# EV75E52A_R3_3-Power.net
KiCad netlist of a schematic drawn in Altium Designer
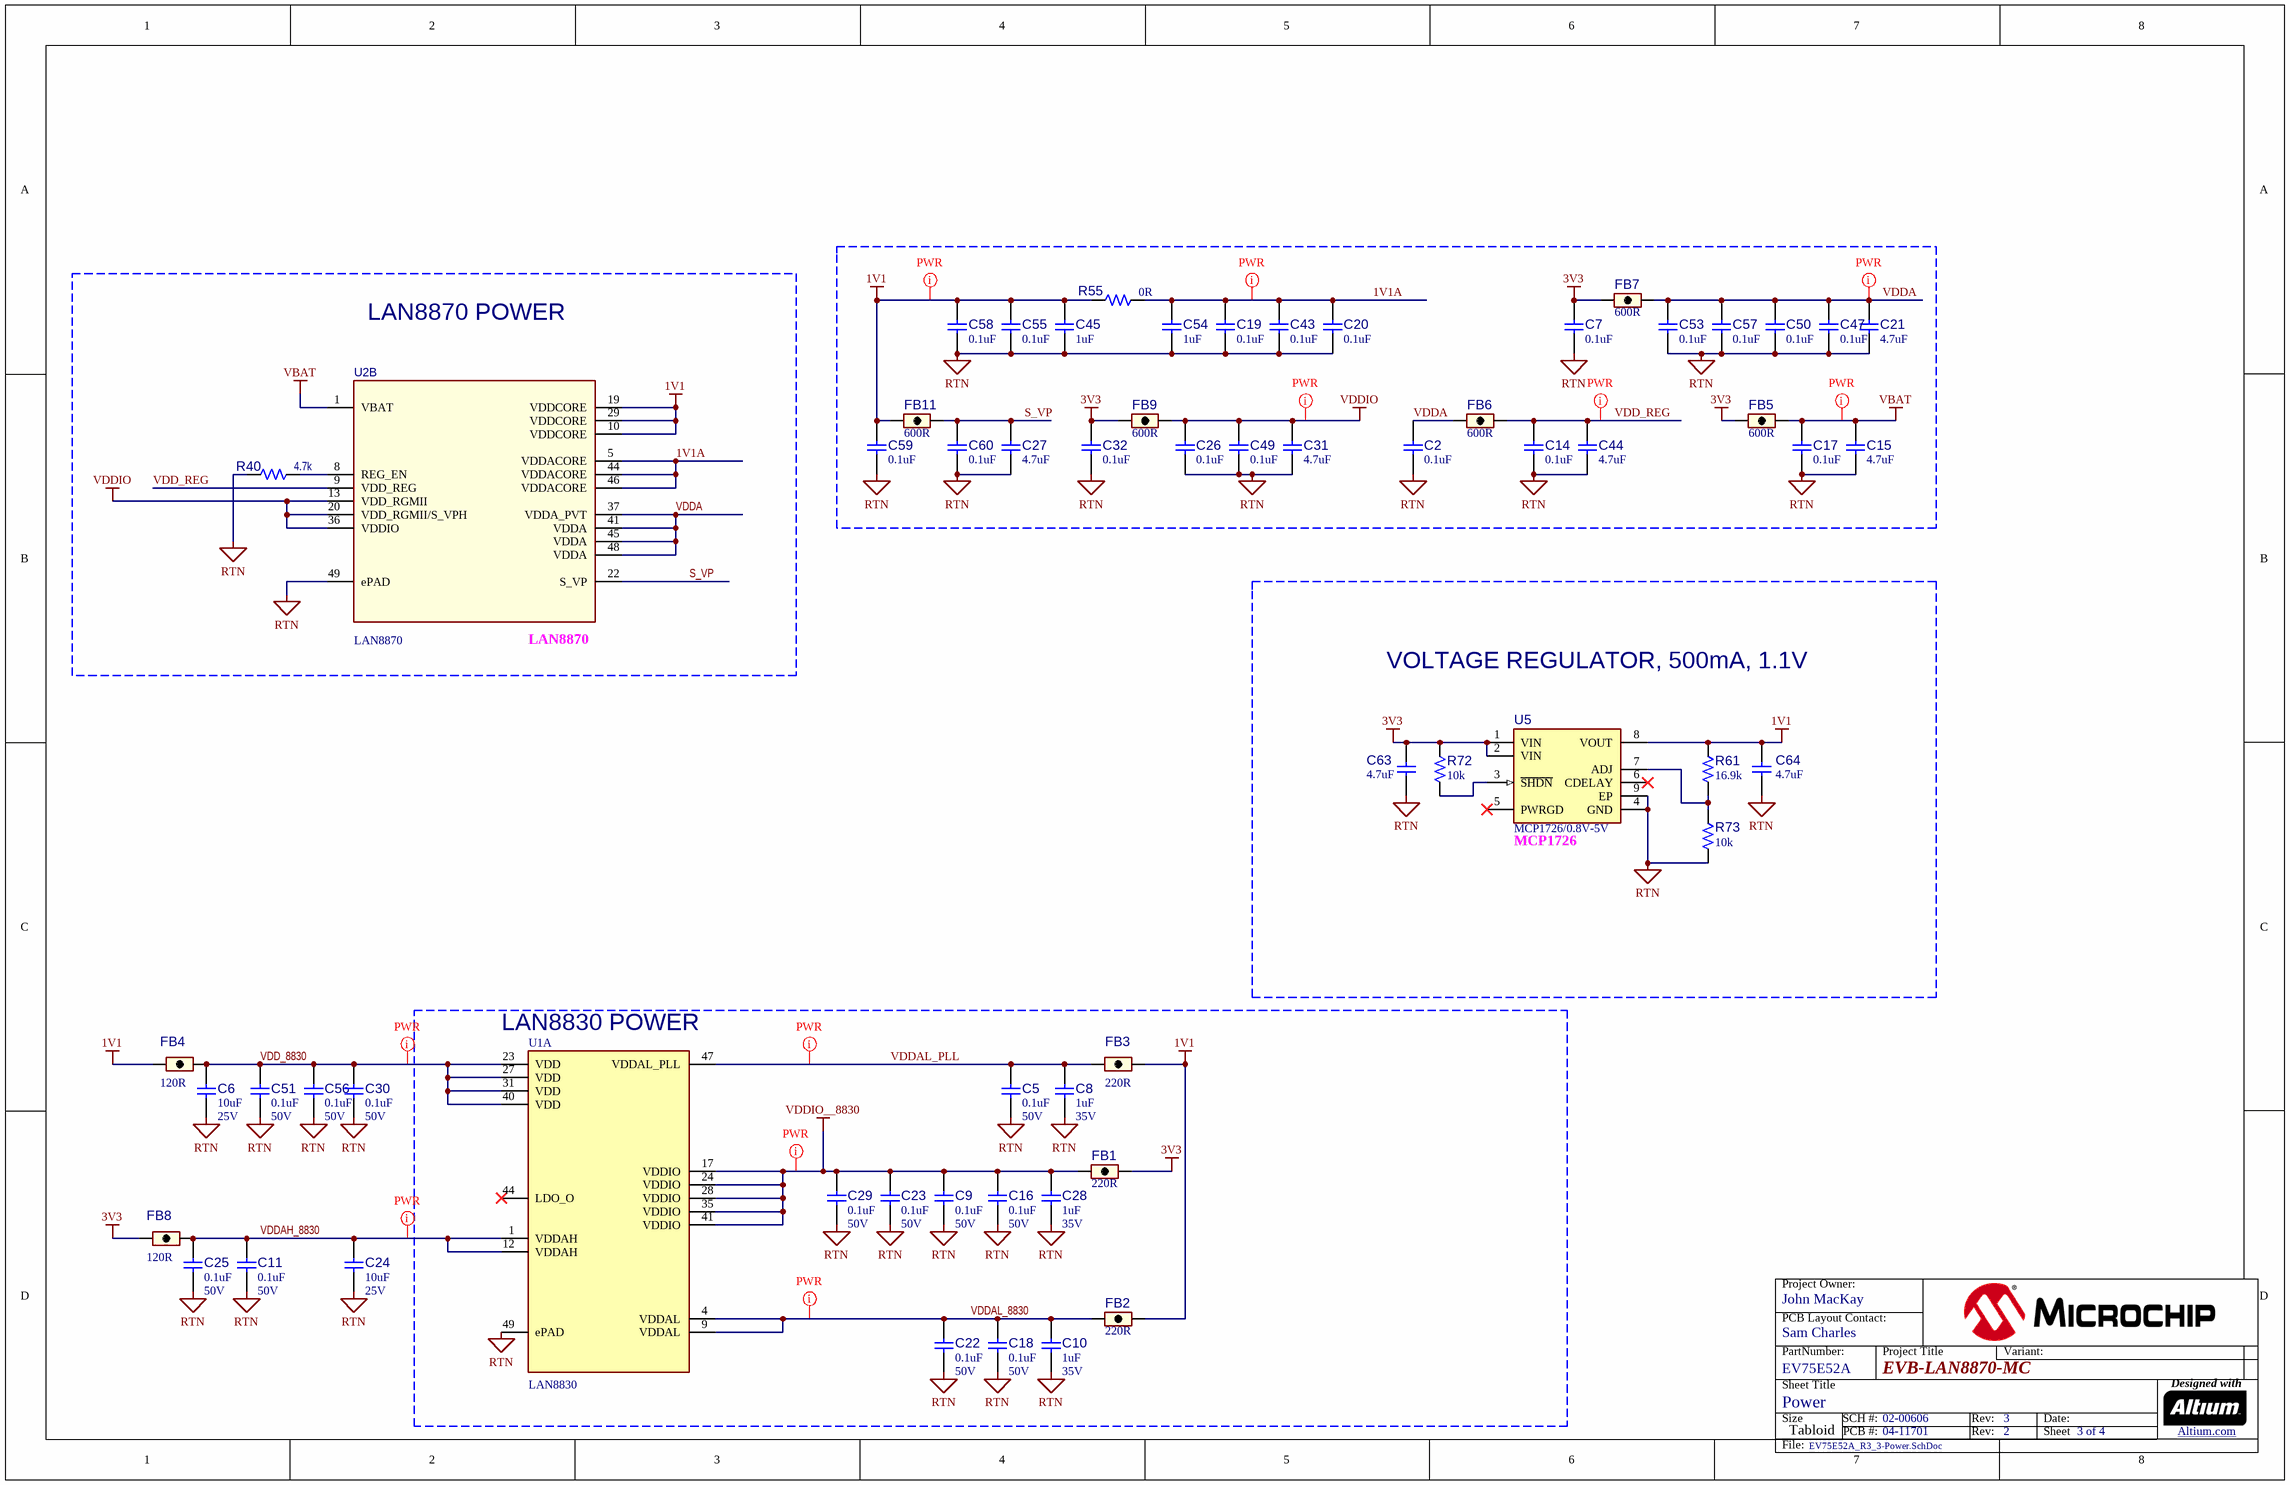
[diagram p0: EV75E52A_R3_3-Power.SchDoc]

(export (version "E")
  (design (tool "Eeschema 10.0.6"))
  (components
    (comp (ref "C2")
      (value "0.1uF")
      (footprint "CAP_C_0402")
      (fields
        (field (name "VOLTAGE") "35V")
        (field (name "TOLERANCE") "10%")
        (field (name "Comment") "Capacitor NP")
        (field (name "OWNER") "Sam Charles")
      )
      (libsource (lib "") (part "Capacitor NP_1"))
    )
    (comp (ref "C5")
      (value "0.1uF")
      (footprint "CAP_C_0402")
      (description "Capacitor")
      (fields
        (field (name "VOLTAGE") "50V")
        (field (name "TOLERANCE") "10%")
        (field (name "Comment") "Capacitor NP")
        (field (name "OWNER") "Jamus Griego")
      )
      (libsource (lib "MCHP-CDB") (part "Capacitor NP"))
    )
    (comp (ref "C6")
      (value "10uF")
      (footprint "CAP_C_0603")
      (description "Capacitor")
      (fields
        (field (name "VOLTAGE") "25V")
        (field (name "TOLERANCE") "±20%")
        (field (name "Comment") "Capacitor NP")
        (field (name "OWNER") "Tim Moffat")
      )
      (libsource (lib "MCHP-CDB") (part "Capacitor NP"))
    )
    (comp (ref "C7")
      (value "0.1uF")
      (footprint "CAP_C_0402")
      (fields
        (field (name "VOLTAGE") "35V")
        (field (name "TOLERANCE") "10%")
        (field (name "Comment") "Capacitor NP")
        (field (name "OWNER") "Sam Charles")
      )
      (libsource (lib "") (part "Capacitor NP_1"))
    )
    (comp (ref "C8")
      (value "1uF")
      (footprint "CAP_C_0402")
      (description "Capacitor")
      (fields
        (field (name "VOLTAGE") "35V")
        (field (name "TOLERANCE") "10%")
        (field (name "Comment") "Capacitor NP")
        (field (name "OWNER") "Sam Charles")
      )
      (libsource (lib "MCHP-CDB") (part "Capacitor NP"))
    )
    (comp (ref "C9")
      (value "0.1uF")
      (footprint "CAP_C_0402")
      (description "Capacitor")
      (fields
        (field (name "VOLTAGE") "50V")
        (field (name "TOLERANCE") "10%")
        (field (name "Comment") "Capacitor NP")
        (field (name "OWNER") "Jamus Griego")
      )
      (libsource (lib "MCHP-CDB") (part "Capacitor NP"))
    )
    (comp (ref "C10")
      (value "1uF")
      (footprint "CAP_C_0402")
      (description "Capacitor")
      (fields
        (field (name "VOLTAGE") "35V")
        (field (name "TOLERANCE") "10%")
        (field (name "Comment") "Capacitor NP")
        (field (name "OWNER") "Sam Charles")
      )
      (libsource (lib "MCHP-CDB") (part "Capacitor NP"))
    )
    (comp (ref "C11")
      (value "0.1uF")
      (footprint "CAP_C_0402")
      (description "Capacitor")
      (fields
        (field (name "VOLTAGE") "50V")
        (field (name "TOLERANCE") "10%")
        (field (name "Comment") "Capacitor NP")
        (field (name "OWNER") "Jamus Griego")
      )
      (libsource (lib "MCHP-CDB") (part "Capacitor NP"))
    )
    (comp (ref "C14")
      (value "0.1uF")
      (footprint "CAP_C_0402")
      (fields
        (field (name "VOLTAGE") "35V")
        (field (name "TOLERANCE") "10%")
        (field (name "Comment") "Capacitor NP")
        (field (name "OWNER") "Sam Charles")
      )
      (libsource (lib "") (part "Capacitor NP_1"))
    )
    (comp (ref "C15")
      (value "4.7uF")
      (footprint "CAP_C_0402")
      (fields
        (field (name "VOLTAGE") "6.3V")
        (field (name "TOLERANCE") "20%")
        (field (name "Comment") "Capacitor NP")
        (field (name "OWNER") "Tad Ahlvers")
      )
      (libsource (lib "") (part "Capacitor NP_1"))
    )
    (comp (ref "C16")
      (value "0.1uF")
      (footprint "CAP_C_0402")
      (description "Capacitor")
      (fields
        (field (name "VOLTAGE") "50V")
        (field (name "TOLERANCE") "10%")
        (field (name "Comment") "Capacitor NP")
        (field (name "OWNER") "Jamus Griego")
      )
      (libsource (lib "MCHP-CDB") (part "Capacitor NP"))
    )
    (comp (ref "C17")
      (value "0.1uF")
      (footprint "CAP_C_0402")
      (fields
        (field (name "VOLTAGE") "35V")
        (field (name "TOLERANCE") "10%")
        (field (name "Comment") "Capacitor NP")
        (field (name "OWNER") "Sam Charles")
      )
      (libsource (lib "") (part "Capacitor NP_1"))
    )
    (comp (ref "C18")
      (value "0.1uF")
      (footprint "CAP_C_0402")
      (description "Capacitor")
      (fields
        (field (name "VOLTAGE") "50V")
        (field (name "TOLERANCE") "10%")
        (field (name "Comment") "Capacitor NP")
        (field (name "OWNER") "Jamus Griego")
      )
      (libsource (lib "MCHP-CDB") (part "Capacitor NP"))
    )
    (comp (ref "C19")
      (value "0.1uF")
      (footprint "CAP_C_0402")
      (fields
        (field (name "VOLTAGE") "35V")
        (field (name "TOLERANCE") "10%")
        (field (name "Comment") "Capacitor NP")
        (field (name "OWNER") "Sam Charles")
      )
      (libsource (lib "") (part "Capacitor NP_1"))
    )
    (comp (ref "C20")
      (value "0.1uF")
      (footprint "CAP_C_0402")
      (fields
        (field (name "VOLTAGE") "35V")
        (field (name "TOLERANCE") "10%")
        (field (name "Comment") "Capacitor NP")
        (field (name "OWNER") "Sam Charles")
      )
      (libsource (lib "") (part "Capacitor NP_1"))
    )
    (comp (ref "C21")
      (value "4.7uF")
      (footprint "CAP_C_0402")
      (fields
        (field (name "VOLTAGE") "6.3V")
        (field (name "TOLERANCE") "20%")
        (field (name "Comment") "Capacitor NP")
        (field (name "OWNER") "Tad Ahlvers")
      )
      (libsource (lib "") (part "Capacitor NP_1"))
    )
    (comp (ref "C22")
      (value "0.1uF")
      (footprint "CAP_C_0402")
      (description "Capacitor")
      (fields
        (field (name "VOLTAGE") "50V")
        (field (name "TOLERANCE") "10%")
        (field (name "Comment") "Capacitor NP")
        (field (name "OWNER") "Jamus Griego")
      )
      (libsource (lib "MCHP-CDB") (part "Capacitor NP"))
    )
    (comp (ref "C23")
      (value "0.1uF")
      (footprint "CAP_C_0402")
      (description "Capacitor")
      (fields
        (field (name "VOLTAGE") "50V")
        (field (name "TOLERANCE") "10%")
        (field (name "Comment") "Capacitor NP")
        (field (name "OWNER") "Jamus Griego")
      )
      (libsource (lib "MCHP-CDB") (part "Capacitor NP"))
    )
    (comp (ref "C24")
      (value "10uF")
      (footprint "CAP_C_0603")
      (description "Capacitor")
      (fields
        (field (name "VOLTAGE") "25V")
        (field (name "TOLERANCE") "±20%")
        (field (name "Comment") "Capacitor NP")
        (field (name "OWNER") "Tim Moffat")
      )
      (libsource (lib "MCHP-CDB") (part "Capacitor NP"))
    )
    (comp (ref "C25")
      (value "0.1uF")
      (footprint "CAP_C_0402")
      (description "Capacitor")
      (fields
        (field (name "VOLTAGE") "50V")
        (field (name "TOLERANCE") "10%")
        (field (name "Comment") "Capacitor NP")
        (field (name "OWNER") "Jamus Griego")
      )
      (libsource (lib "MCHP-CDB") (part "Capacitor NP"))
    )
    (comp (ref "C26")
      (value "0.1uF")
      (footprint "CAP_C_0402")
      (fields
        (field (name "VOLTAGE") "35V")
        (field (name "TOLERANCE") "10%")
        (field (name "Comment") "Capacitor NP")
        (field (name "OWNER") "Sam Charles")
      )
      (libsource (lib "") (part "Capacitor NP_1"))
    )
    (comp (ref "C27")
      (value "4.7uF")
      (footprint "CAP_C_0402")
      (fields
        (field (name "VOLTAGE") "6.3V")
        (field (name "TOLERANCE") "20%")
        (field (name "Comment") "Capacitor NP")
        (field (name "OWNER") "Tad Ahlvers")
      )
      (libsource (lib "") (part "Capacitor NP_1"))
    )
    (comp (ref "C28")
      (value "1uF")
      (footprint "CAP_C_0402")
      (description "Capacitor")
      (fields
        (field (name "VOLTAGE") "35V")
        (field (name "TOLERANCE") "10%")
        (field (name "Comment") "Capacitor NP")
        (field (name "OWNER") "Sam Charles")
      )
      (libsource (lib "MCHP-CDB") (part "Capacitor NP"))
    )
    (comp (ref "C29")
      (value "0.1uF")
      (footprint "CAP_C_0402")
      (description "Capacitor")
      (fields
        (field (name "VOLTAGE") "50V")
        (field (name "TOLERANCE") "10%")
        (field (name "Comment") "Capacitor NP")
        (field (name "OWNER") "Jamus Griego")
      )
      (libsource (lib "MCHP-CDB") (part "Capacitor NP"))
    )
    (comp (ref "C30")
      (value "0.1uF")
      (footprint "CAP_C_0402")
      (description "Capacitor")
      (fields
        (field (name "VOLTAGE") "50V")
        (field (name "TOLERANCE") "10%")
        (field (name "Comment") "Capacitor NP")
        (field (name "OWNER") "Jamus Griego")
      )
      (libsource (lib "MCHP-CDB") (part "Capacitor NP"))
    )
    (comp (ref "C31")
      (value "4.7uF")
      (footprint "CAP_C_0402")
      (fields
        (field (name "VOLTAGE") "6.3V")
        (field (name "TOLERANCE") "20%")
        (field (name "Comment") "Capacitor NP")
        (field (name "OWNER") "Tad Ahlvers")
      )
      (libsource (lib "") (part "Capacitor NP_1"))
    )
    (comp (ref "C32")
      (value "0.1uF")
      (footprint "CAP_C_0402")
      (fields
        (field (name "VOLTAGE") "35V")
        (field (name "TOLERANCE") "10%")
        (field (name "Comment") "Capacitor NP")
        (field (name "OWNER") "Sam Charles")
      )
      (libsource (lib "") (part "Capacitor NP_1"))
    )
    (comp (ref "C43")
      (value "0.1uF")
      (footprint "CAP_C_0402")
      (fields
        (field (name "VOLTAGE") "35V")
        (field (name "TOLERANCE") "10%")
        (field (name "Comment") "Capacitor NP")
        (field (name "OWNER") "Sam Charles")
      )
      (libsource (lib "") (part "Capacitor NP_1"))
    )
    (comp (ref "C44")
      (value "4.7uF")
      (footprint "CAP_C_0402")
      (fields
        (field (name "VOLTAGE") "6.3V")
        (field (name "TOLERANCE") "20%")
        (field (name "Comment") "Capacitor NP")
        (field (name "OWNER") "Tad Ahlvers")
      )
      (libsource (lib "") (part "Capacitor NP_1"))
    )
    (comp (ref "C45")
      (value "1uF")
      (footprint "CAP_C_0402")
      (fields
        (field (name "VOLTAGE") "35V")
        (field (name "TOLERANCE") "10%")
        (field (name "Comment") "Capacitor NP")
        (field (name "OWNER") "Sam Charles")
      )
      (libsource (lib "") (part "Capacitor NP_1"))
    )
    (comp (ref "C47")
      (value "0.1uF")
      (footprint "CAP_C_0402")
      (fields
        (field (name "VOLTAGE") "35V")
        (field (name "TOLERANCE") "10%")
        (field (name "Comment") "Capacitor NP")
        (field (name "OWNER") "Sam Charles")
      )
      (libsource (lib "") (part "Capacitor NP_1"))
    )
    (comp (ref "C49")
      (value "0.1uF")
      (footprint "CAP_C_0402")
      (fields
        (field (name "VOLTAGE") "35V")
        (field (name "TOLERANCE") "10%")
        (field (name "Comment") "Capacitor NP")
        (field (name "OWNER") "Sam Charles")
      )
      (libsource (lib "") (part "Capacitor NP_1"))
    )
    (comp (ref "C50")
      (value "0.1uF")
      (footprint "CAP_C_0402")
      (fields
        (field (name "VOLTAGE") "35V")
        (field (name "TOLERANCE") "10%")
        (field (name "Comment") "Capacitor NP")
        (field (name "OWNER") "Sam Charles")
      )
      (libsource (lib "") (part "Capacitor NP_1"))
    )
    (comp (ref "C51")
      (value "0.1uF")
      (footprint "CAP_C_0402")
      (description "Capacitor")
      (fields
        (field (name "VOLTAGE") "50V")
        (field (name "TOLERANCE") "10%")
        (field (name "Comment") "Capacitor NP")
        (field (name "OWNER") "Jamus Griego")
      )
      (libsource (lib "MCHP-CDB") (part "Capacitor NP"))
    )
    (comp (ref "C53")
      (value "0.1uF")
      (footprint "CAP_C_0402")
      (fields
        (field (name "VOLTAGE") "35V")
        (field (name "TOLERANCE") "10%")
        (field (name "Comment") "Capacitor NP")
        (field (name "OWNER") "Sam Charles")
      )
      (libsource (lib "") (part "Capacitor NP_1"))
    )
    (comp (ref "C54")
      (value "1uF")
      (footprint "CAP_C_0402")
      (fields
        (field (name "VOLTAGE") "35V")
        (field (name "TOLERANCE") "10%")
        (field (name "Comment") "Capacitor NP")
        (field (name "OWNER") "Sam Charles")
      )
      (libsource (lib "") (part "Capacitor NP_1"))
    )
    (comp (ref "C55")
      (value "0.1uF")
      (footprint "CAP_C_0402")
      (fields
        (field (name "VOLTAGE") "35V")
        (field (name "TOLERANCE") "10%")
        (field (name "Comment") "Capacitor NP")
        (field (name "OWNER") "Sam Charles")
      )
      (libsource (lib "") (part "Capacitor NP_1"))
    )
    (comp (ref "C56")
      (value "0.1uF")
      (footprint "CAP_C_0402")
      (description "Capacitor")
      (fields
        (field (name "VOLTAGE") "50V")
        (field (name "TOLERANCE") "10%")
        (field (name "Comment") "Capacitor NP")
        (field (name "OWNER") "Jamus Griego")
      )
      (libsource (lib "MCHP-CDB") (part "Capacitor NP"))
    )
    (comp (ref "C57")
      (value "0.1uF")
      (footprint "CAP_C_0402")
      (fields
        (field (name "VOLTAGE") "35V")
        (field (name "TOLERANCE") "10%")
        (field (name "Comment") "Capacitor NP")
        (field (name "OWNER") "Sam Charles")
      )
      (libsource (lib "") (part "Capacitor NP_1"))
    )
    (comp (ref "C58")
      (value "0.1uF")
      (footprint "CAP_C_0402")
      (fields
        (field (name "VOLTAGE") "35V")
        (field (name "TOLERANCE") "10%")
        (field (name "Comment") "Capacitor NP")
        (field (name "OWNER") "Sam Charles")
      )
      (libsource (lib "") (part "Capacitor NP_1"))
    )
    (comp (ref "C59")
      (value "0.1uF")
      (footprint "CAP_C_0402")
      (fields
        (field (name "VOLTAGE") "35V")
        (field (name "TOLERANCE") "10%")
        (field (name "Comment") "Capacitor NP")
        (field (name "OWNER") "Sam Charles")
      )
      (libsource (lib "") (part "Capacitor NP_1"))
    )
    (comp (ref "C60")
      (value "0.1uF")
      (footprint "CAP_C_0402")
      (fields
        (field (name "VOLTAGE") "35V")
        (field (name "TOLERANCE") "10%")
        (field (name "Comment") "Capacitor NP")
        (field (name "OWNER") "Sam Charles")
      )
      (libsource (lib "") (part "Capacitor NP_1"))
    )
    (comp (ref "C63")
      (value "4.7uF")
      (footprint "CAP_C_0402")
      (fields
        (field (name "VOLTAGE") "6.3V")
        (field (name "TOLERANCE") "20%")
        (field (name "Comment") "Capacitor NP")
        (field (name "OWNER") "Tad Ahlvers")
      )
      (libsource (lib "") (part "Capacitor NP_1"))
    )
    (comp (ref "C64")
      (value "4.7uF")
      (footprint "CAP_C_0402")
      (fields
        (field (name "VOLTAGE") "6.3V")
        (field (name "TOLERANCE") "20%")
        (field (name "Comment") "Capacitor NP")
        (field (name "OWNER") "Tad Ahlvers")
      )
      (libsource (lib "") (part "Capacitor NP_1"))
    )
    (comp (ref "FB1")
      (value "220R")
      (footprint "IND_C_0603")
      (description "FERRITE 180R 1.5A SMD 0603")
      (fields (field (name "Comment") "Ferrite Bead") (field (name "OWNER") "Sam Charles"))
      (libsource (lib "MCHP-CDB") (part "Ferrite Bead"))
    )
    (comp (ref "FB2")
      (value "220R")
      (footprint "IND_C_0603")
      (description "FERRITE 180R 1.5A SMD 0603")
      (fields (field (name "Comment") "Ferrite Bead") (field (name "OWNER") "Sam Charles"))
      (libsource (lib "MCHP-CDB") (part "Ferrite Bead"))
    )
    (comp (ref "FB3")
      (value "220R")
      (footprint "IND_C_0603")
      (fields (field (name "Comment") "Ferrite Bead") (field (name "OWNER") "Sam Charles"))
      (libsource (lib "") (part "Ferrite Bead_1"))
    )
    (comp (ref "FB4")
      (value "120R")
      (footprint "IND_C_0603")
      (description "FERRITE 180R 1.5A SMD 0603")
      (fields (field (name "Comment") "Ferrite Bead") (field (name "OWNER") "Jamus Griego"))
      (libsource (lib "") (part "Ferrite Bead_1"))
    )
    (comp (ref "FB5")
      (value "600R")
      (footprint "IND_C_0603")
      (fields (field (name "Comment") "Ferrite Bead") (field (name "OWNER") "Sam Charles"))
      (libsource (lib "") (part "Ferrite Bead_1"))
    )
    (comp (ref "FB6")
      (value "600R")
      (footprint "IND_C_0603")
      (fields (field (name "Comment") "Ferrite Bead") (field (name "OWNER") "Sam Charles"))
      (libsource (lib "") (part "Ferrite Bead_1"))
    )
    (comp (ref "FB7")
      (value "600R")
      (footprint "IND_C_0603")
      (fields (field (name "Comment") "Ferrite Bead") (field (name "OWNER") "Sam Charles"))
      (libsource (lib "") (part "Ferrite Bead_1"))
    )
    (comp (ref "FB8")
      (value "120R")
      (footprint "IND_C_0603")
      (description "FERRITE 180R 1.5A SMD 0603")
      (fields (field (name "Comment") "Ferrite Bead") (field (name "OWNER") "Jamus Griego"))
      (libsource (lib "") (part "Ferrite Bead_1"))
    )
    (comp (ref "FB9")
      (value "600R")
      (footprint "IND_C_0603")
      (fields (field (name "Comment") "Ferrite Bead") (field (name "OWNER") "Sam Charles"))
      (libsource (lib "") (part "Ferrite Bead_1"))
    )
    (comp (ref "FB11")
      (value "600R")
      (footprint "IND_C_0603")
      (fields (field (name "Comment") "Ferrite Bead") (field (name "OWNER") "Sam Charles"))
      (libsource (lib "") (part "Ferrite Bead_1"))
    )
    (comp (ref "R40")
      (value "4.7k")
      (footprint "RES_C_0402")
      (description "Resistor")
      (fields
        (field (name "TOLERANCE") "1%")
        (field (name "POWER") "1/16W")
        (field (name "OWNER") "Mike Ragsdale")
      )
      (libsource (lib "MCHP-CDB") (part "Resistor"))
    )
    (comp (ref "R55")
      (value "0R")
      (footprint "RES_C_0402")
      (description "Resistor")
      (libsource (lib "MCHP-CDB") (part "Resistor"))
    )
    (comp (ref "R61")
      (value "16.9k")
      (footprint "RES_C_0603")
      (description "Resistor")
      (fields
        (field (name "TOLERANCE") "1%")
        (field (name "VOLTAGE") "75V")
        (field (name "OWNER") "Alexandru Chiser")
      )
      (libsource (lib "") (part "Resistor_1"))
    )
    (comp (ref "R72")
      (value "10k")
      (footprint "RES_C_0402")
      (description "Resistor")
      (fields
        (field (name "TOLERANCE") "1%")
        (field (name "VOLTAGE") "50V")
        (field (name "OWNER") "Brent Lanphear")
      )
      (libsource (lib "MCHP-CDB") (part "Resistor"))
    )
    (comp (ref "R73")
      (value "10k")
      (footprint "RES_C_0603")
      (description "Resistor")
      (fields
        (field (name "TOLERANCE") "1%")
        (field (name "VOLTAGE") "100V")
        (field (name "OWNER") "Jairuz Agang-ang")
      )
      (libsource (lib "") (part "Resistor_1"))
    )
    (comp (ref "U1")
      (value "LAN8830")
      (footprint "QFN-48_7x7_EP5.15x5.15")
      (fields (field (name "Comment") "LAN8830 QFN-48") (field (name "OWNER") "Sam Charles"))
      (libsource (lib "MCHP-CDB") (part "LAN8830 QFN-48"))
    )
    (comp (ref "U2")
      (value "LAN8870")
      (footprint "QFN-48_7x7_EP5.1x5.1")
      (fields
        (field (name "LEGEND NOTE") "LAN8870")
        (field (name "Comment") "LAN8870 QFN-48")
        (field (name "OWNER") "Sam Charles")
      )
      (libsource (lib "LAN8870 QFN-48") (part "LAN8870 QFN-48"))
    )
    (comp (ref "U5")
      (value "MCP1726/0.8V-5V")
      (footprint "DFN-8_3x3")
      (description "LDO ADJ")
      (fields (field (name "LEGEND NOTE") "MCP1726") (field (name "Comment") "MCP172X ADJ DFN-8"))
      (libsource (lib "MCHP-CDB") (part "MCP172X ADJ DFN-8"))
    )
  )
  (nets
    (net (code "1") (name "/1V1A") (class "Default")
      (node (ref "C19") (pin "2") (pinfunction "2_2") (pintype "passive"))
      (node (ref "C20") (pin "2") (pinfunction "2_2") (pintype "passive"))
      (node (ref "C43") (pin "2") (pinfunction "2_2") (pintype "passive"))
      (node (ref "C54") (pin "2") (pinfunction "2_2") (pintype "passive"))
      (node (ref "R55") (pin "2") (pinfunction "2_2") (pintype "passive"))
      (node (ref "U2") (pin "44") (pinfunction "VDDACORE_44") (pintype "power_in"))
      (node (ref "U2") (pin "46") (pinfunction "VDDACORE_46") (pintype "power_in"))
      (node (ref "U2") (pin "5") (pinfunction "VDDACORE_5") (pintype "power_in"))
    )
    (net (code "2") (name "/S_VP") (class "Default")
      (node (ref "C27") (pin "2") (pinfunction "2_2") (pintype "passive"))
      (node (ref "C60") (pin "2") (pinfunction "2_2") (pintype "passive"))
      (node (ref "FB11") (pin "2") (pinfunction "2_2") (pintype "passive"))
      (node (ref "U2") (pin "22") (pinfunction "S_VP_22") (pintype "power_in"))
    )
    (net (code "3") (name "/VDDA") (class "Default")
      (node (ref "C2") (pin "2") (pinfunction "2_2") (pintype "passive"))
      (node (ref "C21") (pin "2") (pinfunction "2_2") (pintype "passive"))
      (node (ref "C47") (pin "2") (pinfunction "2_2") (pintype "passive"))
      (node (ref "C50") (pin "2") (pinfunction "2_2") (pintype "passive"))
      (node (ref "C53") (pin "2") (pinfunction "2_2") (pintype "passive"))
      (node (ref "C57") (pin "2") (pinfunction "2_2") (pintype "passive"))
      (node (ref "FB6") (pin "1") (pinfunction "1_1") (pintype "passive"))
      (node (ref "FB7") (pin "2") (pinfunction "2_2") (pintype "passive"))
      (node (ref "U2") (pin "37") (pinfunction "VDDA_PVT_37") (pintype "power_in"))
      (node (ref "U2") (pin "41") (pinfunction "VDDA_41") (pintype "power_in"))
      (node (ref "U2") (pin "45") (pinfunction "VDDA_45") (pintype "power_in"))
      (node (ref "U2") (pin "48") (pinfunction "VDDA_48") (pintype "power_in"))
    )
    (net (code "4") (name "/VDDAH_8830") (class "Default")
      (node (ref "C11") (pin "2") (pinfunction "2_2") (pintype "passive"))
      (node (ref "C24") (pin "2") (pinfunction "2_2") (pintype "passive"))
      (node (ref "C25") (pin "2") (pinfunction "2_2") (pintype "passive"))
      (node (ref "FB8") (pin "2") (pinfunction "2_2") (pintype "passive"))
      (node (ref "U1") (pin "1") (pinfunction "VDDAH_1") (pintype "power_in"))
      (node (ref "U1") (pin "12") (pinfunction "VDDAH_12") (pintype "power_in"))
    )
    (net (code "5") (name "/VDDAL_8830") (class "Default")
      (node (ref "C10") (pin "2") (pinfunction "2_2") (pintype "passive"))
      (node (ref "C18") (pin "2") (pinfunction "2_2") (pintype "passive"))
      (node (ref "C22") (pin "2") (pinfunction "2_2") (pintype "passive"))
      (node (ref "FB2") (pin "2") (pinfunction "2_2") (pintype "passive"))
      (node (ref "U1") (pin "4") (pinfunction "VDDAL_4") (pintype "power_in"))
      (node (ref "U1") (pin "9") (pinfunction "VDDAL_9") (pintype "power_in"))
    )
    (net (code "6") (name "/VDDAL_PLL") (class "Default")
      (node (ref "C5") (pin "2") (pinfunction "2_2") (pintype "passive"))
      (node (ref "C8") (pin "2") (pinfunction "2_2") (pintype "passive"))
      (node (ref "FB3") (pin "1") (pinfunction "1_1") (pintype "passive"))
      (node (ref "U1") (pin "47") (pinfunction "VDDAL_PLL_47") (pintype "power_in"))
    )
    (net (code "7") (name "/VDD_8830") (class "Default")
      (node (ref "C30") (pin "2") (pinfunction "2_2") (pintype "passive"))
      (node (ref "C51") (pin "2") (pinfunction "2_2") (pintype "passive"))
      (node (ref "C56") (pin "2") (pinfunction "2_2") (pintype "passive"))
      (node (ref "C6") (pin "2") (pinfunction "2_2") (pintype "passive"))
      (node (ref "FB4") (pin "2") (pinfunction "2_2") (pintype "passive"))
      (node (ref "U1") (pin "23") (pinfunction "VDD_23") (pintype "power_in"))
      (node (ref "U1") (pin "27") (pinfunction "VDD_27") (pintype "power_in"))
      (node (ref "U1") (pin "31") (pinfunction "VDD_31") (pintype "power_in"))
      (node (ref "U1") (pin "40") (pinfunction "VDD_40") (pintype "power_in"))
    )
    (net (code "8") (name "/VDD_REG") (class "Default")
      (node (ref "C14") (pin "2") (pinfunction "2_2") (pintype "passive"))
      (node (ref "C44") (pin "2") (pinfunction "2_2") (pintype "passive"))
      (node (ref "FB6") (pin "2") (pinfunction "2_2") (pintype "passive"))
      (node (ref "U2") (pin "9") (pinfunction "VDD_REG_9") (pintype "power_in"))
    )
    (net (code "9") (name "1V1") (class "Default")
      (node (ref "C45") (pin "2") (pinfunction "2_2") (pintype "passive"))
      (node (ref "C55") (pin "2") (pinfunction "2_2") (pintype "passive"))
      (node (ref "C58") (pin "2") (pinfunction "2_2") (pintype "passive"))
      (node (ref "C59") (pin "2") (pinfunction "2_2") (pintype "passive"))
      (node (ref "C64") (pin "2") (pinfunction "2_2") (pintype "passive"))
      (node (ref "FB11") (pin "1") (pinfunction "1_1") (pintype "passive"))
      (node (ref "FB2") (pin "1") (pinfunction "1_1") (pintype "passive"))
      (node (ref "FB3") (pin "2") (pinfunction "2_2") (pintype "passive"))
      (node (ref "FB4") (pin "1") (pinfunction "1_1") (pintype "passive"))
      (node (ref "R55") (pin "1") (pinfunction "1_1") (pintype "passive"))
      (node (ref "R61") (pin "2") (pinfunction "2_2") (pintype "passive"))
      (node (ref "U2") (pin "10") (pinfunction "VDDCORE_10") (pintype "power_in"))
      (node (ref "U2") (pin "19") (pinfunction "VDDCORE_19") (pintype "power_in"))
      (node (ref "U2") (pin "29") (pinfunction "VDDCORE_29") (pintype "power_in"))
      (node (ref "U5") (pin "8") (pinfunction "VOUT_8") (pintype "power_in"))
    )
    (net (code "10") (name "3V3") (class "Default")
      (node (ref "C32") (pin "2") (pinfunction "2_2") (pintype "passive"))
      (node (ref "C63") (pin "2") (pinfunction "2_2") (pintype "passive"))
      (node (ref "C7") (pin "2") (pinfunction "2_2") (pintype "passive"))
      (node (ref "FB1") (pin "1") (pinfunction "1_1") (pintype "passive"))
      (node (ref "FB5") (pin "1") (pinfunction "1_1") (pintype "passive"))
      (node (ref "FB7") (pin "1") (pinfunction "1_1") (pintype "passive"))
      (node (ref "FB8") (pin "1") (pinfunction "1_1") (pintype "passive"))
      (node (ref "FB9") (pin "1") (pinfunction "1_1") (pintype "passive"))
      (node (ref "R72") (pin "2") (pinfunction "2_2") (pintype "passive"))
      (node (ref "U5") (pin "1") (pinfunction "VIN_1") (pintype "power_in"))
      (node (ref "U5") (pin "2") (pinfunction "VIN_2") (pintype "power_in"))
    )
    (net (code "11") (name "Net-(U2B-REG_EN)") (class "Default")
      (node (ref "R40") (pin "1") (pinfunction "1_1") (pintype "passive"))
      (node (ref "U2") (pin "8") (pinfunction "REG_EN_8") (pintype "power_in"))
    )
    (net (code "12") (name "Net-(U5-ADJ)") (class "Default")
      (node (ref "R61") (pin "1") (pinfunction "1_1") (pintype "passive"))
      (node (ref "R73") (pin "2") (pinfunction "2_2") (pintype "passive"))
      (node (ref "U5") (pin "7") (pinfunction "ADJ_7") (pintype "passive"))
    )
    (net (code "13") (name "Net-(U5-~{SHDN})") (class "Default")
      (node (ref "R72") (pin "1") (pinfunction "1_1") (pintype "passive"))
      (node (ref "U5") (pin "3") (pinfunction "~{SHDN}_3") (pintype "input"))
    )
    (net (code "14") (name "RTN") (class "Default")
      (node (ref "C10") (pin "1") (pinfunction "1_1") (pintype "passive"))
      (node (ref "C11") (pin "1") (pinfunction "1_1") (pintype "passive"))
      (node (ref "C14") (pin "1") (pinfunction "1_1") (pintype "passive"))
      (node (ref "C15") (pin "1") (pinfunction "1_1") (pintype "passive"))
      (node (ref "C16") (pin "1") (pinfunction "1_1") (pintype "passive"))
      (node (ref "C17") (pin "1") (pinfunction "1_1") (pintype "passive"))
      (node (ref "C18") (pin "1") (pinfunction "1_1") (pintype "passive"))
      (node (ref "C19") (pin "1") (pinfunction "1_1") (pintype "passive"))
      (node (ref "C2") (pin "1") (pinfunction "1_1") (pintype "passive"))
      (node (ref "C20") (pin "1") (pinfunction "1_1") (pintype "passive"))
      (node (ref "C21") (pin "1") (pinfunction "1_1") (pintype "passive"))
      (node (ref "C22") (pin "1") (pinfunction "1_1") (pintype "passive"))
      (node (ref "C23") (pin "1") (pinfunction "1_1") (pintype "passive"))
      (node (ref "C24") (pin "1") (pinfunction "1_1") (pintype "passive"))
      (node (ref "C25") (pin "1") (pinfunction "1_1") (pintype "passive"))
      (node (ref "C26") (pin "1") (pinfunction "1_1") (pintype "passive"))
      (node (ref "C27") (pin "1") (pinfunction "1_1") (pintype "passive"))
      (node (ref "C28") (pin "1") (pinfunction "1_1") (pintype "passive"))
      (node (ref "C29") (pin "1") (pinfunction "1_1") (pintype "passive"))
      (node (ref "C30") (pin "1") (pinfunction "1_1") (pintype "passive"))
      (node (ref "C31") (pin "1") (pinfunction "1_1") (pintype "passive"))
      (node (ref "C32") (pin "1") (pinfunction "1_1") (pintype "passive"))
      (node (ref "C43") (pin "1") (pinfunction "1_1") (pintype "passive"))
      (node (ref "C44") (pin "1") (pinfunction "1_1") (pintype "passive"))
      (node (ref "C45") (pin "1") (pinfunction "1_1") (pintype "passive"))
      (node (ref "C47") (pin "1") (pinfunction "1_1") (pintype "passive"))
      (node (ref "C49") (pin "1") (pinfunction "1_1") (pintype "passive"))
      (node (ref "C5") (pin "1") (pinfunction "1_1") (pintype "passive"))
      (node (ref "C50") (pin "1") (pinfunction "1_1") (pintype "passive"))
      (node (ref "C51") (pin "1") (pinfunction "1_1") (pintype "passive"))
      (node (ref "C53") (pin "1") (pinfunction "1_1") (pintype "passive"))
      (node (ref "C54") (pin "1") (pinfunction "1_1") (pintype "passive"))
      (node (ref "C55") (pin "1") (pinfunction "1_1") (pintype "passive"))
      (node (ref "C56") (pin "1") (pinfunction "1_1") (pintype "passive"))
      (node (ref "C57") (pin "1") (pinfunction "1_1") (pintype "passive"))
      (node (ref "C58") (pin "1") (pinfunction "1_1") (pintype "passive"))
      (node (ref "C59") (pin "1") (pinfunction "1_1") (pintype "passive"))
      (node (ref "C6") (pin "1") (pinfunction "1_1") (pintype "passive"))
      (node (ref "C60") (pin "1") (pinfunction "1_1") (pintype "passive"))
      (node (ref "C63") (pin "1") (pinfunction "1_1") (pintype "passive"))
      (node (ref "C64") (pin "1") (pinfunction "1_1") (pintype "passive"))
      (node (ref "C7") (pin "1") (pinfunction "1_1") (pintype "passive"))
      (node (ref "C8") (pin "1") (pinfunction "1_1") (pintype "passive"))
      (node (ref "C9") (pin "1") (pinfunction "1_1") (pintype "passive"))
      (node (ref "R40") (pin "2") (pinfunction "2_2") (pintype "passive"))
      (node (ref "R73") (pin "1") (pinfunction "1_1") (pintype "passive"))
      (node (ref "U1") (pin "49") (pinfunction "ePAD_49") (pintype "power_in"))
      (node (ref "U2") (pin "49") (pinfunction "ePAD_49") (pintype "passive"))
      (node (ref "U5") (pin "4") (pinfunction "GND_4") (pintype "power_in"))
      (node (ref "U5") (pin "9") (pinfunction "EP_9") (pintype "passive"))
    )
    (net (code "15") (name "VBAT") (class "Default")
      (node (ref "C15") (pin "2") (pinfunction "2_2") (pintype "passive"))
      (node (ref "C17") (pin "2") (pinfunction "2_2") (pintype "passive"))
      (node (ref "FB5") (pin "2") (pinfunction "2_2") (pintype "passive"))
      (node (ref "U2") (pin "1") (pinfunction "VBAT_1") (pintype "power_in"))
    )
    (net (code "16") (name "VDDIO") (class "Default")
      (node (ref "C26") (pin "2") (pinfunction "2_2") (pintype "passive"))
      (node (ref "C31") (pin "2") (pinfunction "2_2") (pintype "passive"))
      (node (ref "C49") (pin "2") (pinfunction "2_2") (pintype "passive"))
      (node (ref "FB9") (pin "2") (pinfunction "2_2") (pintype "passive"))
      (node (ref "U2") (pin "13") (pinfunction "VDD_RGMII_13") (pintype "power_in"))
      (node (ref "U2") (pin "20") (pinfunction "VDD_RGMII/S_VPH_20") (pintype "power_in"))
      (node (ref "U2") (pin "36") (pinfunction "VDDIO_36") (pintype "power_in"))
    )
    (net (code "17") (name "VDDIO__8830") (class "Default")
      (node (ref "C16") (pin "2") (pinfunction "2_2") (pintype "passive"))
      (node (ref "C23") (pin "2") (pinfunction "2_2") (pintype "passive"))
      (node (ref "C28") (pin "2") (pinfunction "2_2") (pintype "passive"))
      (node (ref "C29") (pin "2") (pinfunction "2_2") (pintype "passive"))
      (node (ref "C9") (pin "2") (pinfunction "2_2") (pintype "passive"))
      (node (ref "FB1") (pin "2") (pinfunction "2_2") (pintype "passive"))
      (node (ref "U1") (pin "17") (pinfunction "VDDIO_17") (pintype "power_in"))
      (node (ref "U1") (pin "24") (pinfunction "VDDIO_24") (pintype "power_in"))
      (node (ref "U1") (pin "28") (pinfunction "VDDIO_28") (pintype "power_in"))
      (node (ref "U1") (pin "35") (pinfunction "VDDIO_35") (pintype "power_in"))
      (node (ref "U1") (pin "41") (pinfunction "VDDIO_41") (pintype "power_in"))
    )
    (net (code "18") (name "unconnected-(U1A-LDO_O-Pad44)") (class "Default")
      (node (ref "U1") (pin "44") (pinfunction "LDO_O_44") (pintype "power_in+no_connect"))
    )
    (net (code "19") (name "unconnected-(U5-CDELAY-Pad6)") (class "Default")
      (node (ref "U5") (pin "6") (pinfunction "CDELAY_6") (pintype "passive+no_connect"))
    )
    (net (code "20") (name "unconnected-(U5-PWRGD-Pad5)") (class "Default")
      (node (ref "U5") (pin "5") (pinfunction "PWRGD_5") (pintype "power_in+no_connect"))
    )
  )
)
